# XIMUF407.net
KiCad netlist of a schematic drawn in Altium Designer
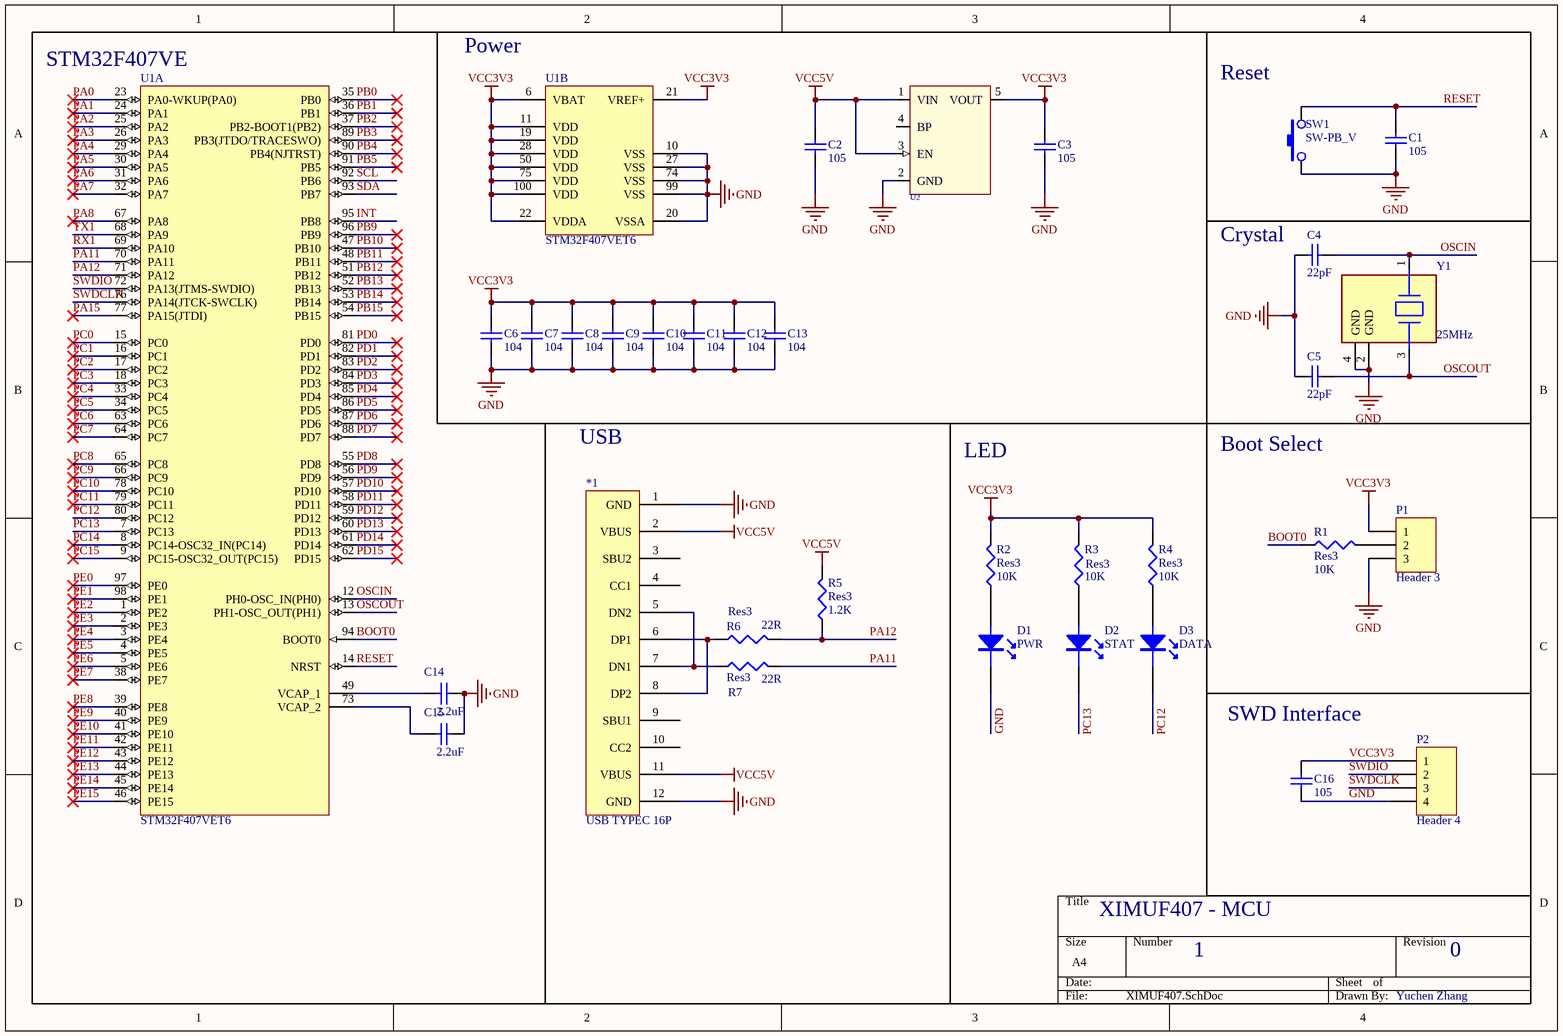
[diagram p0: XIMUF407.SchDoc]

(export (version "E")
  (design (tool "Eeschema 10.0.6"))
  (components
    (comp (ref "*1")
      (value "USB TYPEC 16P")
      (footprint "New footprint 1")
      (libsource (lib "Yuchen Zhang") (part "New symbol 1"))
    )
    (comp (ref "C1")
      (value "105")
      (footprint "C 0603")
      (fields (field (name "PUBLISHER") "Altium Limited"))
      (libsource (lib "stm32原理图库") (part "Cap"))
    )
    (comp (ref "C2")
      (value "105")
      (footprint "C 0603")
      (fields (field (name "PUBLISHER") "Altium Limited"))
      (libsource (lib "stm32原理图库") (part "Cap"))
    )
    (comp (ref "C3")
      (value "105")
      (footprint "C 0603")
      (fields (field (name "PUBLISHER") "Altium Limited"))
      (libsource (lib "stm32原理图库") (part "Cap"))
    )
    (comp (ref "C4")
      (value "22pF")
      (footprint "C 0603")
      (fields (field (name "PUBLISHER") "Altium Limited"))
      (libsource (lib "stm32原理图库") (part "Cap"))
    )
    (comp (ref "C5")
      (value "22pF")
      (footprint "C 0603")
      (fields (field (name "PUBLISHER") "Altium Limited"))
      (libsource (lib "stm32原理图库") (part "Cap"))
    )
    (comp (ref "C6")
      (value "104")
      (footprint "C 0603")
      (fields (field (name "PUBLISHER") "Altium Limited"))
      (libsource (lib "stm32原理图库") (part "Cap"))
    )
    (comp (ref "C7")
      (value "104")
      (footprint "C 0603")
      (fields (field (name "PUBLISHER") "Altium Limited"))
      (libsource (lib "stm32原理图库") (part "Cap"))
    )
    (comp (ref "C8")
      (value "104")
      (footprint "C 0603")
      (fields (field (name "PUBLISHER") "Altium Limited"))
      (libsource (lib "stm32原理图库") (part "Cap"))
    )
    (comp (ref "C9")
      (value "104")
      (footprint "C 0603")
      (fields (field (name "PUBLISHER") "Altium Limited"))
      (libsource (lib "stm32原理图库") (part "Cap"))
    )
    (comp (ref "C10")
      (value "104")
      (footprint "C 0603")
      (fields (field (name "PUBLISHER") "Altium Limited"))
      (libsource (lib "stm32原理图库") (part "Cap"))
    )
    (comp (ref "C11")
      (value "104")
      (footprint "C 0603")
      (fields (field (name "PUBLISHER") "Altium Limited"))
      (libsource (lib "stm32原理图库") (part "Cap"))
    )
    (comp (ref "C12")
      (value "104")
      (footprint "C 0603")
      (fields (field (name "PUBLISHER") "Altium Limited"))
      (libsource (lib "stm32原理图库") (part "Cap"))
    )
    (comp (ref "C13")
      (value "104")
      (footprint "C 0603")
      (fields (field (name "PUBLISHER") "Altium Limited"))
      (libsource (lib "stm32原理图库") (part "Cap"))
    )
    (comp (ref "C14")
      (value "2.2uF")
      (footprint "C 0603")
      (fields (field (name "PUBLISHER") "Altium Limited"))
      (libsource (lib "stm32原理图库") (part "Cap"))
    )
    (comp (ref "C15")
      (value "2.2uF")
      (footprint "C 0603")
      (fields (field (name "PUBLISHER") "Altium Limited"))
      (libsource (lib "stm32原理图库") (part "Cap"))
    )
    (comp (ref "C16")
      (value "105")
      (footprint "C 0603")
      (fields (field (name "PUBLISHER") "Altium Limited"))
      (libsource (lib "stm32原理图库") (part "Cap"))
    )
    (comp (ref "D1") (value "PWR") (footprint "LED 0805G") (libsource (lib "stm32原理图库") (part "LED")))
    (comp (ref "D2") (value "STAT") (footprint "LED 0805G") (libsource (lib "stm32原理图库") (part "LED")))
    (comp (ref "D3") (value "DATA") (footprint "LED 0805G") (libsource (lib "stm32原理图库") (part "LED")))
    (comp (ref "P1")
      (value "Header 3")
      (footprint "HDR1X3")
      (description "Header, 3-Pin")
      (fields (field (name "PUBLISHER") "Altium Limited"))
      (libsource (lib "Miscellaneous Connectors") (part "Header 3"))
    )
    (comp (ref "P2")
      (value "Header 4")
      (footprint "HDR1X4")
      (description "Header, 4-Pin")
      (fields (field (name "PUBLISHER") "Altium Limited"))
      (libsource (lib "Miscellaneous Connectors") (part "Header 4"))
    )
    (comp (ref "R1")
      (value "Res3")
      (footprint "J1-0603")
      (description "Resistor")
      (fields (field (name "ALTIUM_VALUE") "10K") (field (name "PUBLISHER") "Altium Limited"))
      (libsource (lib "Miscellaneous Devices") (part "Res3"))
    )
    (comp (ref "R2")
      (value "Res3")
      (footprint "J1-0603")
      (description "Resistor")
      (fields (field (name "ALTIUM_VALUE") "10K") (field (name "PUBLISHER") "Altium Limited"))
      (libsource (lib "Miscellaneous Devices") (part "Res3"))
    )
    (comp (ref "R3")
      (value "Res3")
      (footprint "J1-0603")
      (description "Resistor")
      (fields (field (name "ALTIUM_VALUE") "10K") (field (name "PUBLISHER") "Altium Limited"))
      (libsource (lib "Miscellaneous Devices") (part "Res3"))
    )
    (comp (ref "R4")
      (value "Res3")
      (footprint "J1-0603")
      (description "Resistor")
      (fields (field (name "ALTIUM_VALUE") "10K") (field (name "PUBLISHER") "Altium Limited"))
      (libsource (lib "Miscellaneous Devices") (part "Res3"))
    )
    (comp (ref "R5")
      (value "Res3")
      (footprint "J1-0603")
      (description "Resistor")
      (fields (field (name "ALTIUM_VALUE") "1.2K") (field (name "PUBLISHER") "Altium Limited"))
      (libsource (lib "Miscellaneous Devices") (part "Res3"))
    )
    (comp (ref "R6")
      (value "Res3")
      (footprint "J1-0603")
      (description "Resistor")
      (fields (field (name "ALTIUM_VALUE") "22R") (field (name "PUBLISHER") "Altium Limited"))
      (libsource (lib "Miscellaneous Devices") (part "Res3"))
    )
    (comp (ref "R7")
      (value "Res3")
      (footprint "J1-0603")
      (description "Resistor")
      (fields (field (name "ALTIUM_VALUE") "22R") (field (name "PUBLISHER") "Altium Limited"))
      (libsource (lib "Miscellaneous Devices") (part "Res3"))
    )
    (comp (ref "SW1")
      (value "SW-PB_V")
      (footprint "TSW SMD-3*6*2.5")
      (libsource (lib "stm32原理图库") (part "SW-PB_V"))
    )
    (comp (ref "U1")
      (value "STM32F407VET6")
      (footprint "STM-LQFP100_M")
      (fields (field (name "MANUFACTURER") "STMicroelectronics"))
      (libsource (lib "Altium Content Vault") (part "MC-ARM-STM32F40X_41X-SQ100"))
    )
    (comp (ref "U2")
      (value "RT9193")
      (footprint "SOT23-5L")
      (fields (field (name "ICA_PARTNUM") "$$2191094$$RT9193-15CU5") (field (name "PART NUMBER") "TMP-13"))
      (libsource (lib "stm32原理图库") (part "RT9193X_5P"))
    )
    (comp (ref "Y1")
      (value "25MHz")
      (footprint "FP-TSX-3225-MFG")
      (description "CRYSTAL 16.00 MHZ 9PF SMD")
      (fields
        (field (name "MANUFACTURER PART NUMBER") "TSX-3225 16.0000MF18X-AC0")
        (field (name "OCTOPART") "https://octopart.com/tsx-3225+16.0000mf18x-ac0-epson-58756552")
      )
      (libsource (lib "Altium Content Vault") (part "a9e65936d6f6a8cd8abf4b50f2664b9"))
    )
  )
  (nets
    (net (code "1") (name "/BOOT0") (class "Default")
      (node (ref "R1") (pin "1") (pinfunction "1_1") (pintype "passive"))
      (node (ref "U1") (pin "94") (pinfunction "BOOT0_94") (pintype "input"))
    )
    (net (code "2") (name "/INT") (class "Default")
      (node (ref "U1") (pin "95") (pinfunction "PB8_95") (pintype "bidirectional"))
    )
    (net (code "3") (name "/OSCIN") (class "Default")
      (node (ref "C4") (pin "1") (pinfunction "1_1") (pintype "passive"))
      (node (ref "U1") (pin "12") (pinfunction "PH0-OSC_IN(PH0)_12") (pintype "bidirectional"))
      (node (ref "Y1") (pin "1") (pinfunction "1_1") (pintype "passive"))
    )
    (net (code "4") (name "/OSCOUT") (class "Default")
      (node (ref "C5") (pin "1") (pinfunction "1_1") (pintype "passive"))
      (node (ref "U1") (pin "13") (pinfunction "PH1-OSC_OUT(PH1)_13") (pintype "bidirectional"))
      (node (ref "Y1") (pin "3") (pinfunction "3_3") (pintype "passive"))
    )
    (net (code "5") (name "/PA0") (class "Default")
      (node (ref "U1") (pin "23") (pinfunction "PA0-WKUP(PA0)_23") (pintype "bidirectional+no_connect"))
    )
    (net (code "6") (name "/PA1") (class "Default")
      (node (ref "U1") (pin "24") (pinfunction "PA1_24") (pintype "bidirectional+no_connect"))
    )
    (net (code "7") (name "/PA2") (class "Default")
      (node (ref "U1") (pin "25") (pinfunction "PA2_25") (pintype "bidirectional+no_connect"))
    )
    (net (code "8") (name "/PA3") (class "Default")
      (node (ref "U1") (pin "26") (pinfunction "PA3_26") (pintype "bidirectional+no_connect"))
    )
    (net (code "9") (name "/PA4") (class "Default")
      (node (ref "U1") (pin "29") (pinfunction "PA4_29") (pintype "bidirectional+no_connect"))
    )
    (net (code "10") (name "/PA5") (class "Default")
      (node (ref "U1") (pin "30") (pinfunction "PA5_30") (pintype "bidirectional+no_connect"))
    )
    (net (code "11") (name "/PA6") (class "Default")
      (node (ref "U1") (pin "31") (pinfunction "PA6_31") (pintype "bidirectional+no_connect"))
    )
    (net (code "12") (name "/PA7") (class "Default")
      (node (ref "U1") (pin "32") (pinfunction "PA7_32") (pintype "bidirectional+no_connect"))
    )
    (net (code "13") (name "/PA8") (class "Default")
      (node (ref "U1") (pin "67") (pinfunction "PA8_67") (pintype "bidirectional+no_connect"))
    )
    (net (code "14") (name "/PA11") (class "Default")
      (node (ref "R7") (pin "2") (pinfunction "2_2") (pintype "passive"))
      (node (ref "U1") (pin "70") (pinfunction "PA11_70") (pintype "bidirectional"))
    )
    (net (code "15") (name "/PA12") (class "Default")
      (node (ref "R5") (pin "1") (pinfunction "1_1") (pintype "passive"))
      (node (ref "R6") (pin "2") (pinfunction "2_2") (pintype "passive"))
      (node (ref "U1") (pin "71") (pinfunction "PA12_71") (pintype "bidirectional"))
    )
    (net (code "16") (name "/PA15") (class "Default")
      (node (ref "U1") (pin "77") (pinfunction "PA15(JTDI)_77") (pintype "bidirectional+no_connect"))
    )
    (net (code "17") (name "/PB0") (class "Default")
      (node (ref "U1") (pin "35") (pinfunction "PB0_35") (pintype "bidirectional+no_connect"))
    )
    (net (code "18") (name "/PB1") (class "Default")
      (node (ref "U1") (pin "36") (pinfunction "PB1_36") (pintype "bidirectional+no_connect"))
    )
    (net (code "19") (name "/PB2") (class "Default")
      (node (ref "U1") (pin "37") (pinfunction "PB2-BOOT1(PB2)_37") (pintype "bidirectional+no_connect"))
    )
    (net (code "20") (name "/PB3") (class "Default")
      (node (ref "U1") (pin "89") (pinfunction "PB3(JTDO/TRACESWO)_89") (pintype "bidirectional+no_connect"))
    )
    (net (code "21") (name "/PB4") (class "Default")
      (node (ref "U1") (pin "90") (pinfunction "PB4(NJTRST)_90") (pintype "bidirectional+no_connect"))
    )
    (net (code "22") (name "/PB5") (class "Default")
      (node (ref "U1") (pin "91") (pinfunction "PB5_91") (pintype "bidirectional+no_connect"))
    )
    (net (code "23") (name "/PB9") (class "Default")
      (node (ref "U1") (pin "96") (pinfunction "PB9_96") (pintype "bidirectional+no_connect"))
    )
    (net (code "24") (name "/PB10") (class "Default")
      (node (ref "U1") (pin "47") (pinfunction "PB10_47") (pintype "bidirectional+no_connect"))
    )
    (net (code "25") (name "/PB11") (class "Default")
      (node (ref "U1") (pin "48") (pinfunction "PB11_48") (pintype "bidirectional+no_connect"))
    )
    (net (code "26") (name "/PB12") (class "Default")
      (node (ref "U1") (pin "51") (pinfunction "PB12_51") (pintype "bidirectional+no_connect"))
    )
    (net (code "27") (name "/PB13") (class "Default")
      (node (ref "U1") (pin "52") (pinfunction "PB13_52") (pintype "bidirectional+no_connect"))
    )
    (net (code "28") (name "/PB14") (class "Default")
      (node (ref "U1") (pin "53") (pinfunction "PB14_53") (pintype "bidirectional+no_connect"))
    )
    (net (code "29") (name "/PB15") (class "Default")
      (node (ref "U1") (pin "54") (pinfunction "PB15_54") (pintype "bidirectional+no_connect"))
    )
    (net (code "30") (name "/PC0") (class "Default")
      (node (ref "U1") (pin "15") (pinfunction "PC0_15") (pintype "bidirectional+no_connect"))
    )
    (net (code "31") (name "/PC1") (class "Default")
      (node (ref "U1") (pin "16") (pinfunction "PC1_16") (pintype "bidirectional+no_connect"))
    )
    (net (code "32") (name "/PC2") (class "Default")
      (node (ref "U1") (pin "17") (pinfunction "PC2_17") (pintype "bidirectional+no_connect"))
    )
    (net (code "33") (name "/PC3") (class "Default")
      (node (ref "U1") (pin "18") (pinfunction "PC3_18") (pintype "bidirectional+no_connect"))
    )
    (net (code "34") (name "/PC4") (class "Default")
      (node (ref "U1") (pin "33") (pinfunction "PC4_33") (pintype "bidirectional+no_connect"))
    )
    (net (code "35") (name "/PC5") (class "Default")
      (node (ref "U1") (pin "34") (pinfunction "PC5_34") (pintype "bidirectional+no_connect"))
    )
    (net (code "36") (name "/PC6") (class "Default")
      (node (ref "U1") (pin "63") (pinfunction "PC6_63") (pintype "bidirectional+no_connect"))
    )
    (net (code "37") (name "/PC7") (class "Default")
      (node (ref "U1") (pin "64") (pinfunction "PC7_64") (pintype "bidirectional+no_connect"))
    )
    (net (code "38") (name "/PC8") (class "Default")
      (node (ref "U1") (pin "65") (pinfunction "PC8_65") (pintype "bidirectional+no_connect"))
    )
    (net (code "39") (name "/PC9") (class "Default")
      (node (ref "U1") (pin "66") (pinfunction "PC9_66") (pintype "bidirectional+no_connect"))
    )
    (net (code "40") (name "/PC10") (class "Default")
      (node (ref "U1") (pin "78") (pinfunction "PC10_78") (pintype "bidirectional+no_connect"))
    )
    (net (code "41") (name "/PC11") (class "Default")
      (node (ref "U1") (pin "79") (pinfunction "PC11_79") (pintype "bidirectional+no_connect"))
    )
    (net (code "42") (name "/PC12") (class "Default")
      (node (ref "D3") (pin "2") (pinfunction "2_2") (pintype "passive"))
      (node (ref "U1") (pin "80") (pinfunction "PC12_80") (pintype "bidirectional"))
    )
    (net (code "43") (name "/PC13") (class "Default")
      (node (ref "D2") (pin "2") (pinfunction "2_2") (pintype "passive"))
      (node (ref "U1") (pin "7") (pinfunction "PC13_7") (pintype "bidirectional"))
    )
    (net (code "44") (name "/PC14") (class "Default")
      (node (ref "U1") (pin "8") (pinfunction "PC14-OSC32_IN(PC14)_8") (pintype "bidirectional+no_connect"))
    )
    (net (code "45") (name "/PC15") (class "Default")
      (node (ref "U1") (pin "9") (pinfunction "PC15-OSC32_OUT(PC15)_9") (pintype "bidirectional+no_connect"))
    )
    (net (code "46") (name "/PD0") (class "Default")
      (node (ref "U1") (pin "81") (pinfunction "PD0_81") (pintype "bidirectional+no_connect"))
    )
    (net (code "47") (name "/PD1") (class "Default")
      (node (ref "U1") (pin "82") (pinfunction "PD1_82") (pintype "bidirectional+no_connect"))
    )
    (net (code "48") (name "/PD2") (class "Default")
      (node (ref "U1") (pin "83") (pinfunction "PD2_83") (pintype "bidirectional+no_connect"))
    )
    (net (code "49") (name "/PD3") (class "Default")
      (node (ref "U1") (pin "84") (pinfunction "PD3_84") (pintype "bidirectional+no_connect"))
    )
    (net (code "50") (name "/PD4") (class "Default")
      (node (ref "U1") (pin "85") (pinfunction "PD4_85") (pintype "bidirectional+no_connect"))
    )
    (net (code "51") (name "/PD5") (class "Default")
      (node (ref "U1") (pin "86") (pinfunction "PD5_86") (pintype "bidirectional+no_connect"))
    )
    (net (code "52") (name "/PD6") (class "Default")
      (node (ref "U1") (pin "87") (pinfunction "PD6_87") (pintype "bidirectional+no_connect"))
    )
    (net (code "53") (name "/PD7") (class "Default")
      (node (ref "U1") (pin "88") (pinfunction "PD7_88") (pintype "bidirectional+no_connect"))
    )
    (net (code "54") (name "/PD8") (class "Default")
      (node (ref "U1") (pin "55") (pinfunction "PD8_55") (pintype "bidirectional+no_connect"))
    )
    (net (code "55") (name "/PD9") (class "Default")
      (node (ref "U1") (pin "56") (pinfunction "PD9_56") (pintype "bidirectional+no_connect"))
    )
    (net (code "56") (name "/PD10") (class "Default")
      (node (ref "U1") (pin "57") (pinfunction "PD10_57") (pintype "bidirectional+no_connect"))
    )
    (net (code "57") (name "/PD11") (class "Default")
      (node (ref "U1") (pin "58") (pinfunction "PD11_58") (pintype "bidirectional+no_connect"))
    )
    (net (code "58") (name "/PD12") (class "Default")
      (node (ref "U1") (pin "59") (pinfunction "PD12_59") (pintype "bidirectional+no_connect"))
    )
    (net (code "59") (name "/PD13") (class "Default")
      (node (ref "U1") (pin "60") (pinfunction "PD13_60") (pintype "bidirectional+no_connect"))
    )
    (net (code "60") (name "/PD14") (class "Default")
      (node (ref "U1") (pin "61") (pinfunction "PD14_61") (pintype "bidirectional+no_connect"))
    )
    (net (code "61") (name "/PD15") (class "Default")
      (node (ref "U1") (pin "62") (pinfunction "PD15_62") (pintype "bidirectional+no_connect"))
    )
    (net (code "62") (name "/PE0") (class "Default")
      (node (ref "U1") (pin "97") (pinfunction "PE0_97") (pintype "bidirectional+no_connect"))
    )
    (net (code "63") (name "/PE1") (class "Default")
      (node (ref "U1") (pin "98") (pinfunction "PE1_98") (pintype "bidirectional+no_connect"))
    )
    (net (code "64") (name "/PE2") (class "Default")
      (node (ref "U1") (pin "1") (pinfunction "PE2_1") (pintype "bidirectional+no_connect"))
    )
    (net (code "65") (name "/PE3") (class "Default")
      (node (ref "U1") (pin "2") (pinfunction "PE3_2") (pintype "bidirectional+no_connect"))
    )
    (net (code "66") (name "/PE4") (class "Default")
      (node (ref "U1") (pin "3") (pinfunction "PE4_3") (pintype "bidirectional+no_connect"))
    )
    (net (code "67") (name "/PE5") (class "Default")
      (node (ref "U1") (pin "4") (pinfunction "PE5_4") (pintype "bidirectional+no_connect"))
    )
    (net (code "68") (name "/PE6") (class "Default")
      (node (ref "U1") (pin "5") (pinfunction "PE6_5") (pintype "bidirectional+no_connect"))
    )
    (net (code "69") (name "/PE7") (class "Default")
      (node (ref "U1") (pin "38") (pinfunction "PE7_38") (pintype "bidirectional+no_connect"))
    )
    (net (code "70") (name "/PE8") (class "Default")
      (node (ref "U1") (pin "39") (pinfunction "PE8_39") (pintype "bidirectional+no_connect"))
    )
    (net (code "71") (name "/PE9") (class "Default")
      (node (ref "U1") (pin "40") (pinfunction "PE9_40") (pintype "bidirectional+no_connect"))
    )
    (net (code "72") (name "/PE10") (class "Default")
      (node (ref "U1") (pin "41") (pinfunction "PE10_41") (pintype "bidirectional+no_connect"))
    )
    (net (code "73") (name "/PE11") (class "Default")
      (node (ref "U1") (pin "42") (pinfunction "PE11_42") (pintype "bidirectional+no_connect"))
    )
    (net (code "74") (name "/PE12") (class "Default")
      (node (ref "U1") (pin "43") (pinfunction "PE12_43") (pintype "bidirectional+no_connect"))
    )
    (net (code "75") (name "/PE13") (class "Default")
      (node (ref "U1") (pin "44") (pinfunction "PE13_44") (pintype "bidirectional+no_connect"))
    )
    (net (code "76") (name "/PE14") (class "Default")
      (node (ref "U1") (pin "45") (pinfunction "PE14_45") (pintype "bidirectional+no_connect"))
    )
    (net (code "77") (name "/PE15") (class "Default")
      (node (ref "U1") (pin "46") (pinfunction "PE15_46") (pintype "bidirectional+no_connect"))
    )
    (net (code "78") (name "/RESET") (class "Default")
      (node (ref "C1") (pin "2") (pinfunction "2_2") (pintype "passive"))
      (node (ref "SW1") (pin "2") (pinfunction "2_2") (pintype "passive"))
      (node (ref "U1") (pin "14") (pinfunction "NRST_14") (pintype "bidirectional"))
    )
    (net (code "79") (name "/RX1") (class "Default")
      (node (ref "U1") (pin "69") (pinfunction "PA10_69") (pintype "bidirectional"))
    )
    (net (code "80") (name "/SCL") (class "Default")
      (node (ref "U1") (pin "92") (pinfunction "PB6_92") (pintype "bidirectional"))
    )
    (net (code "81") (name "/SDA") (class "Default")
      (node (ref "U1") (pin "93") (pinfunction "PB7_93") (pintype "bidirectional"))
    )
    (net (code "82") (name "/SWDCLK") (class "Default")
      (node (ref "P2") (pin "3") (pinfunction "3_3") (pintype "passive"))
      (node (ref "U1") (pin "76") (pinfunction "PA14(JTCK-SWCLK)_76") (pintype "bidirectional"))
    )
    (net (code "83") (name "/SWDIO") (class "Default")
      (node (ref "P2") (pin "2") (pinfunction "2_2") (pintype "passive"))
      (node (ref "U1") (pin "72") (pinfunction "PA13(JTMS-SWDIO)_72") (pintype "bidirectional"))
    )
    (net (code "84") (name "/TX1") (class "Default")
      (node (ref "U1") (pin "68") (pinfunction "PA9_68") (pintype "bidirectional"))
    )
    (net (code "85") (name "GND") (class "Default")
      (node (ref "*1") (pin "1") (pinfunction "GND_1") (pintype "passive"))
      (node (ref "*1") (pin "12") (pinfunction "GND_12") (pintype "passive"))
      (node (ref "C1") (pin "1") (pinfunction "1_1") (pintype "passive"))
      (node (ref "C10") (pin "1") (pinfunction "1_1") (pintype "passive"))
      (node (ref "C11") (pin "1") (pinfunction "1_1") (pintype "passive"))
      (node (ref "C12") (pin "1") (pinfunction "1_1") (pintype "passive"))
      (node (ref "C13") (pin "1") (pinfunction "1_1") (pintype "passive"))
      (node (ref "C14") (pin "1") (pinfunction "1_1") (pintype "passive"))
      (node (ref "C15") (pin "1") (pinfunction "1_1") (pintype "passive"))
      (node (ref "C16") (pin "1") (pinfunction "1_1") (pintype "passive"))
      (node (ref "C2") (pin "1") (pinfunction "1_1") (pintype "passive"))
      (node (ref "C3") (pin "1") (pinfunction "1_1") (pintype "passive"))
      (node (ref "C4") (pin "2") (pinfunction "2_2") (pintype "passive"))
      (node (ref "C5") (pin "2") (pinfunction "2_2") (pintype "passive"))
      (node (ref "C6") (pin "1") (pinfunction "1_1") (pintype "passive"))
      (node (ref "C7") (pin "1") (pinfunction "1_1") (pintype "passive"))
      (node (ref "C8") (pin "1") (pinfunction "1_1") (pintype "passive"))
      (node (ref "C9") (pin "1") (pinfunction "1_1") (pintype "passive"))
      (node (ref "D1") (pin "2") (pinfunction "2_2") (pintype "passive"))
      (node (ref "P1") (pin "3") (pinfunction "3_3") (pintype "passive"))
      (node (ref "P2") (pin "4") (pinfunction "4_4") (pintype "passive"))
      (node (ref "SW1") (pin "1") (pinfunction "1_1") (pintype "passive"))
      (node (ref "U1") (pin "10") (pinfunction "VSS_10") (pintype "power_in"))
      (node (ref "U1") (pin "20") (pinfunction "VSSA_20") (pintype "power_in"))
      (node (ref "U1") (pin "27") (pinfunction "VSS_27") (pintype "power_in"))
      (node (ref "U1") (pin "74") (pinfunction "VSS_74") (pintype "power_in"))
      (node (ref "U1") (pin "99") (pinfunction "VSS_99") (pintype "power_in"))
      (node (ref "U2") (pin "2") (pinfunction "GND_2") (pintype "power_in"))
      (node (ref "Y1") (pin "2") (pinfunction "GND_2") (pintype "power_in"))
      (node (ref "Y1") (pin "4") (pinfunction "GND_4") (pintype "power_in"))
    )
    (net (code "86") (name "Net-(*1-DN1)") (class "Default")
      (node (ref "*1") (pin "5") (pinfunction "DN2_5") (pintype "passive"))
      (node (ref "*1") (pin "7") (pinfunction "DN1_7") (pintype "passive"))
      (node (ref "R7") (pin "1") (pinfunction "1_1") (pintype "passive"))
    )
    (net (code "87") (name "Net-(*1-DP1)") (class "Default")
      (node (ref "*1") (pin "6") (pinfunction "DP1_6") (pintype "passive"))
      (node (ref "*1") (pin "8") (pinfunction "DP2_8") (pintype "passive"))
      (node (ref "R6") (pin "1") (pinfunction "1_1") (pintype "passive"))
    )
    (net (code "88") (name "Net-(D1-Pad1)") (class "Default")
      (node (ref "D1") (pin "1") (pinfunction "1_1") (pintype "passive"))
      (node (ref "R2") (pin "1") (pinfunction "1_1") (pintype "passive"))
    )
    (net (code "89") (name "Net-(D2-Pad1)") (class "Default")
      (node (ref "D2") (pin "1") (pinfunction "1_1") (pintype "passive"))
      (node (ref "R3") (pin "1") (pinfunction "1_1") (pintype "passive"))
    )
    (net (code "90") (name "Net-(D3-Pad1)") (class "Default")
      (node (ref "D3") (pin "1") (pinfunction "1_1") (pintype "passive"))
      (node (ref "R4") (pin "1") (pinfunction "1_1") (pintype "passive"))
    )
    (net (code "91") (name "Net-(P1-Pad2)") (class "Default")
      (node (ref "P1") (pin "2") (pinfunction "2_2") (pintype "passive"))
      (node (ref "R1") (pin "2") (pinfunction "2_2") (pintype "passive"))
    )
    (net (code "92") (name "Net-(U1A-VCAP_1)") (class "Default")
      (node (ref "C14") (pin "2") (pinfunction "2_2") (pintype "passive"))
      (node (ref "U1") (pin "49") (pinfunction "VCAP_1_49") (pintype "power_in"))
    )
    (net (code "93") (name "Net-(U1A-VCAP_2)") (class "Default")
      (node (ref "C15") (pin "2") (pinfunction "2_2") (pintype "passive"))
      (node (ref "U1") (pin "73") (pinfunction "VCAP_2_73") (pintype "power_in"))
    )
    (net (code "94") (name "VCC3V3") (class "Default")
      (node (ref "C10") (pin "2") (pinfunction "2_2") (pintype "passive"))
      (node (ref "C11") (pin "2") (pinfunction "2_2") (pintype "passive"))
      (node (ref "C12") (pin "2") (pinfunction "2_2") (pintype "passive"))
      (node (ref "C13") (pin "2") (pinfunction "2_2") (pintype "passive"))
      (node (ref "C16") (pin "2") (pinfunction "2_2") (pintype "passive"))
      (node (ref "C3") (pin "2") (pinfunction "2_2") (pintype "passive"))
      (node (ref "C6") (pin "2") (pinfunction "2_2") (pintype "passive"))
      (node (ref "C7") (pin "2") (pinfunction "2_2") (pintype "passive"))
      (node (ref "C8") (pin "2") (pinfunction "2_2") (pintype "passive"))
      (node (ref "C9") (pin "2") (pinfunction "2_2") (pintype "passive"))
      (node (ref "P1") (pin "1") (pinfunction "1_1") (pintype "passive"))
      (node (ref "P2") (pin "1") (pinfunction "1_1") (pintype "passive"))
      (node (ref "R2") (pin "2") (pinfunction "2_2") (pintype "passive"))
      (node (ref "R3") (pin "2") (pinfunction "2_2") (pintype "passive"))
      (node (ref "R4") (pin "2") (pinfunction "2_2") (pintype "passive"))
      (node (ref "U1") (pin "100") (pinfunction "VDD_100") (pintype "power_in"))
      (node (ref "U1") (pin "11") (pinfunction "VDD_11") (pintype "power_in"))
      (node (ref "U1") (pin "19") (pinfunction "VDD_19") (pintype "power_in"))
      (node (ref "U1") (pin "21") (pinfunction "VREF+_21") (pintype "power_in"))
      (node (ref "U1") (pin "22") (pinfunction "VDDA_22") (pintype "power_in"))
      (node (ref "U1") (pin "28") (pinfunction "VDD_28") (pintype "power_in"))
      (node (ref "U1") (pin "50") (pinfunction "VDD_50") (pintype "power_in"))
      (node (ref "U1") (pin "6") (pinfunction "VBAT_6") (pintype "power_in"))
      (node (ref "U1") (pin "75") (pinfunction "VDD_75") (pintype "power_in"))
      (node (ref "U2") (pin "5") (pinfunction "VOUT_5") (pintype "power_in"))
    )
    (net (code "95") (name "VCC5V") (class "Default")
      (node (ref "*1") (pin "11") (pinfunction "VBUS_11") (pintype "passive"))
      (node (ref "*1") (pin "2") (pinfunction "VBUS_2") (pintype "passive"))
      (node (ref "C2") (pin "2") (pinfunction "2_2") (pintype "passive"))
      (node (ref "R5") (pin "2") (pinfunction "2_2") (pintype "passive"))
      (node (ref "U2") (pin "1") (pinfunction "VIN_1") (pintype "power_in"))
      (node (ref "U2") (pin "3") (pinfunction "EN_3") (pintype "input"))
    )
    (net (code "96") (name "unconnected-(*1-CC1-Pad4)") (class "Default")
      (node (ref "*1") (pin "4") (pinfunction "CC1_4") (pintype "passive"))
    )
    (net (code "97") (name "unconnected-(*1-CC2-Pad10)") (class "Default")
      (node (ref "*1") (pin "10") (pinfunction "CC2_10") (pintype "passive"))
    )
    (net (code "98") (name "unconnected-(*1-SBU1-Pad9)") (class "Default")
      (node (ref "*1") (pin "9") (pinfunction "SBU1_9") (pintype "passive"))
    )
    (net (code "99") (name "unconnected-(*1-SBU2-Pad3)") (class "Default")
      (node (ref "*1") (pin "3") (pinfunction "SBU2_3") (pintype "passive"))
    )
    (net (code "100") (name "unconnected-(U2-BP-Pad4)") (class "Default")
      (node (ref "U2") (pin "4") (pinfunction "BP_4") (pintype "passive"))
    )
  )
)
